# btle_board.net
KiCad netlist of a schematic drawn in EAGLE
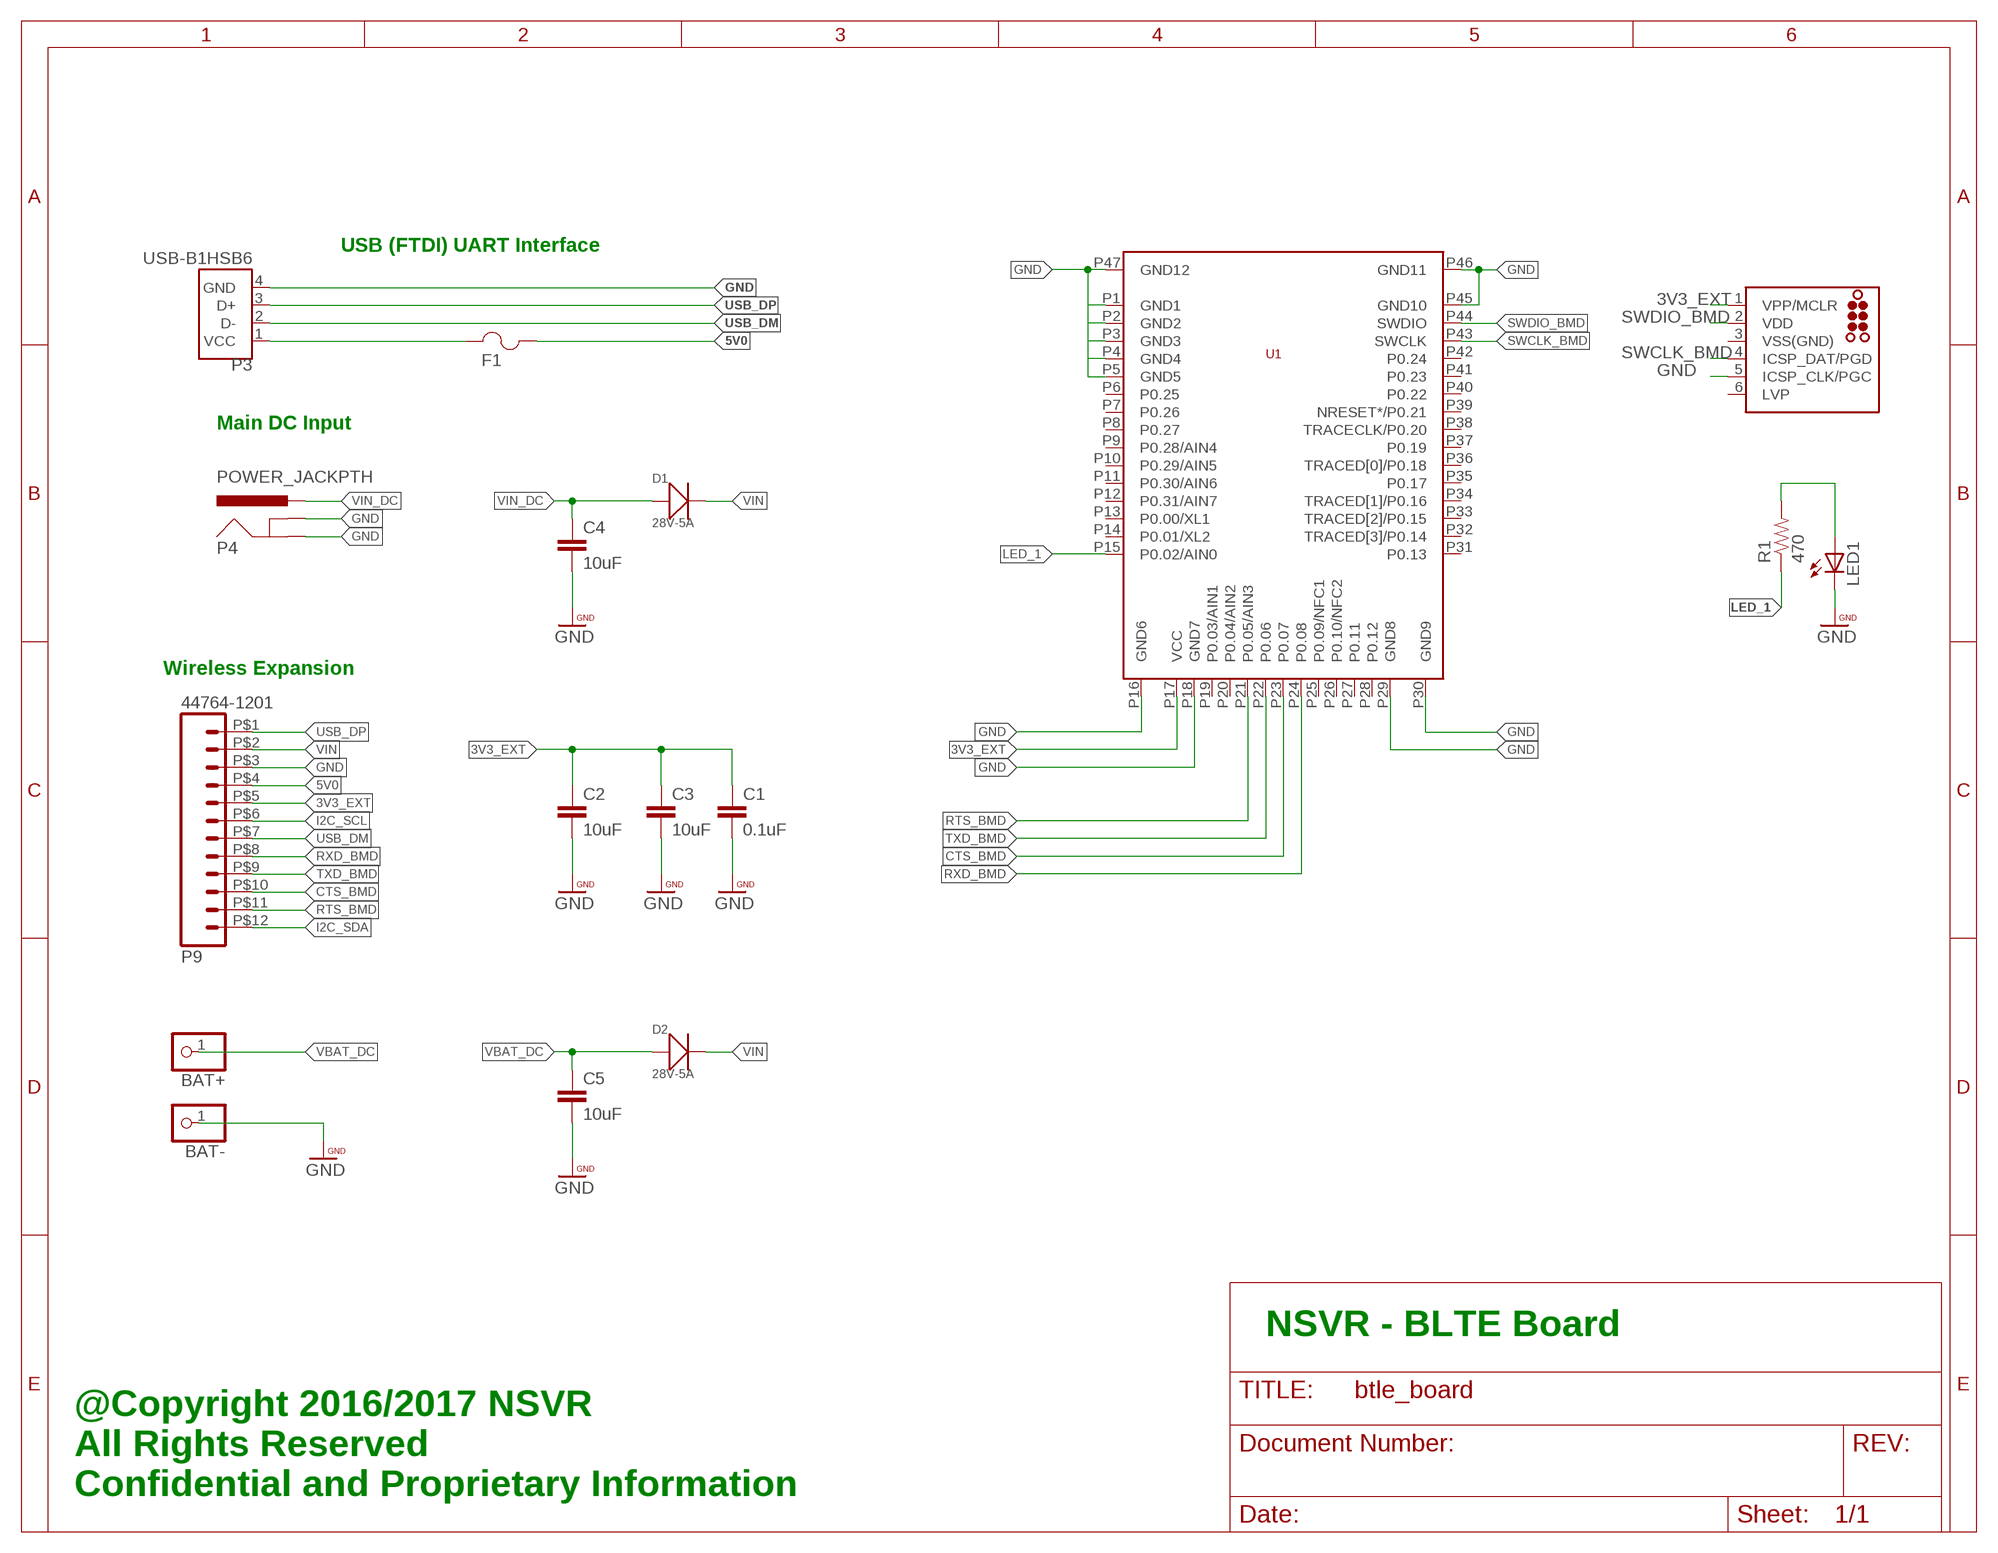
[diagram p0: schematic, sheet 1]

(export (version "E")
  (design (tool "Eeschema 10.0.6"))
  (components
    (comp (ref "BAT+")
      (value "WPAD-1-PTH")
      (footprint "eagle-import:WPAD-1-PTH-2.54")
      (libsource (lib "eagle-import") (part "WPAD-1-PTH"))
    )
    (comp (ref "BAT-")
      (value "WPAD-1-PTH")
      (footprint "eagle-import:WPAD-1-PTH-2.54")
      (libsource (lib "eagle-import") (part "WPAD-1-PTH"))
    )
    (comp (ref "C1")
      (value "0.1uF")
      (footprint "eagle-import:0603-CAP")
      (libsource (lib "eagle-import") (part "CAP0603-CAP"))
    )
    (comp (ref "C2")
      (value "10uF")
      (footprint "eagle-import:0603-CAP")
      (libsource (lib "eagle-import") (part "CAP0603-CAP"))
    )
    (comp (ref "C3")
      (value "10uF")
      (footprint "eagle-import:0603-CAP")
      (libsource (lib "eagle-import") (part "CAP0603-CAP"))
    )
    (comp (ref "C4")
      (value "10uF")
      (footprint "eagle-import:0603-CAP")
      (libsource (lib "eagle-import") (part "CAP0603-CAP"))
    )
    (comp (ref "C5")
      (value "10uF")
      (footprint "eagle-import:0603-CAP")
      (libsource (lib "eagle-import") (part "CAP0603-CAP"))
    )
    (comp (ref "D1")
      (value "28V-5A")
      (footprint "eagle-import:DO-214AA")
      (fields (field (name "MPN") "SS54B"))
      (libsource (lib "eagle-import") (part "SMD-DIODE-SCHOTTKY-28V-5A(DO-214AA)"))
    )
    (comp (ref "D2")
      (value "28V-5A")
      (footprint "eagle-import:DO-214AA")
      (fields (field (name "MPN") "SS54B"))
      (libsource (lib "eagle-import") (part "SMD-DIODE-SCHOTTKY-28V-5A(DO-214AA)"))
    )
    (comp (ref "F1")
      (value "1206L050YR")
      (footprint "eagle-import:1206LSERIES")
      (fields (field (name "COPYRIGHT") "Copyright C 2015 Accelerated Designs. All rights reserved"))
      (libsource (lib "eagle-import") (part "1206L050YR"))
    )
    (comp (ref "LED1")
      (value "LEDCHIP-LED0603")
      (footprint "eagle-import:CHIP-LED0603")
      (libsource (lib "eagle-import") (part "LEDCHIP-LED0603"))
    )
    (comp (ref "P1")
      (value "TC2030-MCP-NL")
      (footprint "eagle-import:TC2030-MCP-NL")
      (libsource (lib "eagle-import") (part "TC2030-MCP-NL"))
    )
    (comp (ref "P3")
      (value "USB-B1HSB6")
      (footprint "eagle-import:OST_USB-B1HSB6")
      (fields (field (name "MF") "On Shore Technology"))
      (libsource (lib "eagle-import") (part "USB-B1HSB6"))
    )
    (comp (ref "P4")
      (value "POWER_JACKPTH")
      (footprint "eagle-import:POWER_JACK_PTH")
      (libsource (lib "eagle-import") (part "POWER_JACKPTH"))
    )
    (comp (ref "P9")
      (value "44764-1201")
      (footprint "eagle-import:44764-1201")
      (libsource (lib "eagle-import") (part "44764-1201"))
    )
    (comp (ref "R1")
      (value "470")
      (footprint "eagle-import:EIA-0402")
      (libsource (lib "eagle-import") (part "RESISTOR0402-TYP"))
    )
    (comp (ref "U1")
      (value "BMD-300")
      (footprint "eagle-import:BMD-300")
      (libsource (lib "eagle-import") (part "BMD-300"))
    )
  )
  (nets
    (net (code "1") (name "/VSS(GND)") (class "Default")
      (node (ref "P1") (pin "3") (pinfunction "VSS(GND)_3") (pintype "power_in"))
    )
    (net (code "2") (name "3V3_EXT") (class "Default")
      (node (ref "C1") (pin "1") (pinfunction "1_1") (pintype "passive"))
      (node (ref "C2") (pin "1") (pinfunction "1_1") (pintype "passive"))
      (node (ref "C3") (pin "1") (pinfunction "1_1") (pintype "passive"))
      (node (ref "P1") (pin "1") (pinfunction "VPP/MCLR_1") (pintype "passive"))
      (node (ref "P9") (pin "P$5") (pinfunction "5_P$5") (pintype "passive"))
      (node (ref "U1") (pin "P17") (pinfunction "VCC_P17") (pintype "bidirectional"))
    )
    (net (code "3") (name "5V0") (class "Default")
      (node (ref "F1") (pin "2") (pinfunction "2_2") (pintype "passive"))
      (node (ref "P9") (pin "P$4") (pinfunction "4_P$4") (pintype "passive"))
    )
    (net (code "4") (name "CTS_BMD") (class "Default")
      (node (ref "P9") (pin "P$10") (pinfunction "10_P$10") (pintype "passive"))
      (node (ref "U1") (pin "P23") (pinfunction "P0.07_P23") (pintype "bidirectional"))
    )
    (net (code "5") (name "GND") (class "Default")
      (node (ref "BAT-") (pin "1") (pinfunction "1_1") (pintype "passive"))
      (node (ref "C1") (pin "2") (pinfunction "2_2") (pintype "passive"))
      (node (ref "C2") (pin "2") (pinfunction "2_2") (pintype "passive"))
      (node (ref "C3") (pin "2") (pinfunction "2_2") (pintype "passive"))
      (node (ref "C4") (pin "2") (pinfunction "2_2") (pintype "passive"))
      (node (ref "C5") (pin "2") (pinfunction "2_2") (pintype "passive"))
      (node (ref "LED1") (pin "C") (pinfunction "C_C") (pintype "passive"))
      (node (ref "P1") (pin "5") (pinfunction "ICSP_CLK/PGC_5") (pintype "output"))
      (node (ref "P3") (pin "4") (pinfunction "GND_4") (pintype "power_in"))
      (node (ref "P4") (pin "GND") (pinfunction "GND_GND") (pintype "bidirectional"))
      (node (ref "P4") (pin "GNDBREAK") (pinfunction "GNDBREAK_GNDBREAK") (pintype "bidirectional"))
      (node (ref "P9") (pin "P$3") (pinfunction "3_P$3") (pintype "passive"))
      (node (ref "U1") (pin "P1") (pinfunction "GND1_P1") (pintype "bidirectional"))
      (node (ref "U1") (pin "P16") (pinfunction "GND6_P16") (pintype "bidirectional"))
      (node (ref "U1") (pin "P18") (pinfunction "GND7_P18") (pintype "bidirectional"))
      (node (ref "U1") (pin "P2") (pinfunction "GND2_P2") (pintype "bidirectional"))
      (node (ref "U1") (pin "P29") (pinfunction "GND8_P29") (pintype "bidirectional"))
      (node (ref "U1") (pin "P3") (pinfunction "GND3_P3") (pintype "bidirectional"))
      (node (ref "U1") (pin "P30") (pinfunction "GND9_P30") (pintype "bidirectional"))
      (node (ref "U1") (pin "P4") (pinfunction "GND4_P4") (pintype "bidirectional"))
      (node (ref "U1") (pin "P45") (pinfunction "GND10_P45") (pintype "bidirectional"))
      (node (ref "U1") (pin "P46") (pinfunction "GND11_P46") (pintype "bidirectional"))
      (node (ref "U1") (pin "P47") (pinfunction "GND12_P47") (pintype "bidirectional"))
      (node (ref "U1") (pin "P5") (pinfunction "GND5_P5") (pintype "bidirectional"))
    )
    (net (code "6") (name "I2C_SCL") (class "Default")
      (node (ref "P9") (pin "P$6") (pinfunction "6_P$6") (pintype "passive"))
    )
    (net (code "7") (name "I2C_SDA") (class "Default")
      (node (ref "P9") (pin "P$12") (pinfunction "12_P$12") (pintype "passive"))
    )
    (net (code "8") (name "LED_1") (class "Default")
      (node (ref "R1") (pin "1") (pinfunction "1_1") (pintype "passive"))
      (node (ref "U1") (pin "P15") (pinfunction "P0.02/AIN0_P15") (pintype "bidirectional"))
    )
    (net (code "9") (name "Net-(LED1-PadA)") (class "Default")
      (node (ref "LED1") (pin "A") (pinfunction "A_A") (pintype "passive"))
      (node (ref "R1") (pin "2") (pinfunction "2_2") (pintype "passive"))
    )
    (net (code "10") (name "Net-(P3-VCC)") (class "Default")
      (node (ref "F1") (pin "1") (pinfunction "1_1") (pintype "passive"))
      (node (ref "P3") (pin "1") (pinfunction "VCC_1") (pintype "power_in"))
    )
    (net (code "11") (name "RTS_BMD") (class "Default")
      (node (ref "P9") (pin "P$11") (pinfunction "11_P$11") (pintype "passive"))
      (node (ref "U1") (pin "P21") (pinfunction "P0.05/AIN3_P21") (pintype "bidirectional"))
    )
    (net (code "12") (name "RXD_BMD") (class "Default")
      (node (ref "P9") (pin "P$8") (pinfunction "8_P$8") (pintype "passive"))
      (node (ref "U1") (pin "P24") (pinfunction "P0.08_P24") (pintype "bidirectional"))
    )
    (net (code "13") (name "SWCLK_BMD") (class "Default")
      (node (ref "P1") (pin "4") (pinfunction "ICSP_DAT/PGD_4") (pintype "bidirectional"))
      (node (ref "U1") (pin "P43") (pinfunction "SWCLK_P43") (pintype "bidirectional"))
    )
    (net (code "14") (name "SWDIO_BMD") (class "Default")
      (node (ref "P1") (pin "2") (pinfunction "VDD_2") (pintype "power_in"))
      (node (ref "U1") (pin "P44") (pinfunction "SWDIO_P44") (pintype "bidirectional"))
    )
    (net (code "15") (name "TXD_BMD") (class "Default")
      (node (ref "P9") (pin "P$9") (pinfunction "9_P$9") (pintype "passive"))
      (node (ref "U1") (pin "P22") (pinfunction "P0.06_P22") (pintype "bidirectional"))
    )
    (net (code "16") (name "USB_DM") (class "Default")
      (node (ref "P3") (pin "2") (pinfunction "D-_2") (pintype "bidirectional"))
      (node (ref "P9") (pin "P$7") (pinfunction "7_P$7") (pintype "passive"))
    )
    (net (code "17") (name "USB_DP") (class "Default")
      (node (ref "P3") (pin "3") (pinfunction "D+_3") (pintype "bidirectional"))
      (node (ref "P9") (pin "P$1") (pinfunction "1_P$1") (pintype "passive"))
    )
    (net (code "18") (name "VBAT_DC") (class "Default")
      (node (ref "BAT+") (pin "1") (pinfunction "1_1") (pintype "passive"))
      (node (ref "C5") (pin "1") (pinfunction "1_1") (pintype "passive"))
      (node (ref "D2") (pin "+") (pinfunction "+_+") (pintype "passive"))
    )
    (net (code "19") (name "VIN") (class "Default")
      (node (ref "D1") (pin "-") (pinfunction "-_-") (pintype "passive"))
      (node (ref "D2") (pin "-") (pinfunction "-_-") (pintype "passive"))
      (node (ref "P9") (pin "P$2") (pinfunction "2_P$2") (pintype "passive"))
    )
    (net (code "20") (name "VIN_DC") (class "Default")
      (node (ref "C4") (pin "1") (pinfunction "1_1") (pintype "passive"))
      (node (ref "D1") (pin "+") (pinfunction "+_+") (pintype "passive"))
      (node (ref "P4") (pin "PWR") (pinfunction "PWR_PWR") (pintype "bidirectional"))
    )
    (net (code "21") (name "unconnected-(P1-LVP-Pad6)") (class "Default")
      (node (ref "P1") (pin "6") (pinfunction "LVP_6") (pintype "bidirectional"))
    )
    (net (code "22") (name "unconnected-(U1-NRESET*{slash}P0.21-PadP39)") (class "Default")
      (node (ref "U1") (pin "P39") (pinfunction "NRESET*/P0.21_P39") (pintype "bidirectional"))
    )
    (net (code "23") (name "unconnected-(U1-P0.00{slash}XL1-PadP13)") (class "Default")
      (node (ref "U1") (pin "P13") (pinfunction "P0.00/XL1_P13") (pintype "bidirectional"))
    )
    (net (code "24") (name "unconnected-(U1-P0.01{slash}XL2-PadP14)") (class "Default")
      (node (ref "U1") (pin "P14") (pinfunction "P0.01/XL2_P14") (pintype "bidirectional"))
    )
    (net (code "25") (name "unconnected-(U1-P0.03{slash}AIN1-PadP19)") (class "Default")
      (node (ref "U1") (pin "P19") (pinfunction "P0.03/AIN1_P19") (pintype "bidirectional"))
    )
    (net (code "26") (name "unconnected-(U1-P0.04{slash}AIN2-PadP20)") (class "Default")
      (node (ref "U1") (pin "P20") (pinfunction "P0.04/AIN2_P20") (pintype "bidirectional"))
    )
    (net (code "27") (name "unconnected-(U1-P0.09{slash}NFC1-PadP25)") (class "Default")
      (node (ref "U1") (pin "P25") (pinfunction "P0.09/NFC1_P25") (pintype "bidirectional"))
    )
    (net (code "28") (name "unconnected-(U1-P0.10{slash}NFC2-PadP26)") (class "Default")
      (node (ref "U1") (pin "P26") (pinfunction "P0.10/NFC2_P26") (pintype "bidirectional"))
    )
    (net (code "29") (name "unconnected-(U1-P0.11-PadP27)") (class "Default")
      (node (ref "U1") (pin "P27") (pinfunction "P0.11_P27") (pintype "bidirectional"))
    )
    (net (code "30") (name "unconnected-(U1-P0.12-PadP28)") (class "Default")
      (node (ref "U1") (pin "P28") (pinfunction "P0.12_P28") (pintype "bidirectional"))
    )
    (net (code "31") (name "unconnected-(U1-P0.13-PadP31)") (class "Default")
      (node (ref "U1") (pin "P31") (pinfunction "P0.13_P31") (pintype "bidirectional"))
    )
    (net (code "32") (name "unconnected-(U1-P0.17-PadP35)") (class "Default")
      (node (ref "U1") (pin "P35") (pinfunction "P0.17_P35") (pintype "bidirectional"))
    )
    (net (code "33") (name "unconnected-(U1-P0.19-PadP37)") (class "Default")
      (node (ref "U1") (pin "P37") (pinfunction "P0.19_P37") (pintype "bidirectional"))
    )
    (net (code "34") (name "unconnected-(U1-P0.22-PadP40)") (class "Default")
      (node (ref "U1") (pin "P40") (pinfunction "P0.22_P40") (pintype "bidirectional"))
    )
    (net (code "35") (name "unconnected-(U1-P0.23-PadP41)") (class "Default")
      (node (ref "U1") (pin "P41") (pinfunction "P0.23_P41") (pintype "bidirectional"))
    )
    (net (code "36") (name "unconnected-(U1-P0.24-PadP42)") (class "Default")
      (node (ref "U1") (pin "P42") (pinfunction "P0.24_P42") (pintype "bidirectional"))
    )
    (net (code "37") (name "unconnected-(U1-P0.25-PadP6)") (class "Default")
      (node (ref "U1") (pin "P6") (pinfunction "P0.25_P6") (pintype "bidirectional"))
    )
    (net (code "38") (name "unconnected-(U1-P0.26-PadP7)") (class "Default")
      (node (ref "U1") (pin "P7") (pinfunction "P0.26_P7") (pintype "bidirectional"))
    )
    (net (code "39") (name "unconnected-(U1-P0.27-PadP8)") (class "Default")
      (node (ref "U1") (pin "P8") (pinfunction "P0.27_P8") (pintype "bidirectional"))
    )
    (net (code "40") (name "unconnected-(U1-P0.28{slash}AIN4-PadP9)") (class "Default")
      (node (ref "U1") (pin "P9") (pinfunction "P0.28/AIN4_P9") (pintype "bidirectional"))
    )
    (net (code "41") (name "unconnected-(U1-P0.29{slash}AIN5-PadP10)") (class "Default")
      (node (ref "U1") (pin "P10") (pinfunction "P0.29/AIN5_P10") (pintype "bidirectional"))
    )
    (net (code "42") (name "unconnected-(U1-P0.30{slash}AIN6-PadP11)") (class "Default")
      (node (ref "U1") (pin "P11") (pinfunction "P0.30/AIN6_P11") (pintype "bidirectional"))
    )
    (net (code "43") (name "unconnected-(U1-P0.31{slash}AIN7-PadP12)") (class "Default")
      (node (ref "U1") (pin "P12") (pinfunction "P0.31/AIN7_P12") (pintype "bidirectional"))
    )
    (net (code "44") (name "unconnected-(U1-TRACECLK{slash}P0.20-PadP38)") (class "Default")
      (node (ref "U1") (pin "P38") (pinfunction "TRACECLK/P0.20_P38") (pintype "bidirectional"))
    )
    (net (code "45") (name "unconnected-(U1-TRACED[0]{slash}P0.18-PadP36)") (class "Default")
      (node (ref "U1") (pin "P36") (pinfunction "TRACED[0]/P0.18_P36") (pintype "bidirectional"))
    )
    (net (code "46") (name "unconnected-(U1-TRACED[1]{slash}P0.16-PadP34)") (class "Default")
      (node (ref "U1") (pin "P34") (pinfunction "TRACED[1]/P0.16_P34") (pintype "bidirectional"))
    )
    (net (code "47") (name "unconnected-(U1-TRACED[2]{slash}P0.15-PadP33)") (class "Default")
      (node (ref "U1") (pin "P33") (pinfunction "TRACED[2]/P0.15_P33") (pintype "bidirectional"))
    )
    (net (code "48") (name "unconnected-(U1-TRACED[3]{slash}P0.14-PadP32)") (class "Default")
      (node (ref "U1") (pin "P32") (pinfunction "TRACED[3]/P0.14_P32") (pintype "bidirectional"))
    )
  )
)
